# 14_BUZZER.net
KiCad netlist of a schematic drawn in Altium Designer
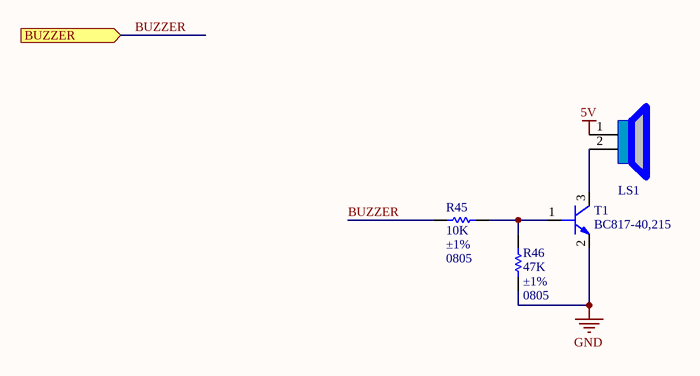
[diagram p0: 14.BUZZER.SchDoc]

(export (version "E")
  (design (tool "Eeschema 10.0.6"))
  (components
    (comp (ref "LS1")
      (value "BUZZER")
      (footprint "BUZZER_12MM")
      (description "AUDIO MAGNETIC INDICATOR 4-7V TH")
      (fields (field (name "PART NUMBER") "SAUD00001") (field (name "VOLTAGE") "5VDC"))
      (libsource (lib "ComponentDatabase") (part "BUZZER"))
    )
    (comp (ref "R45")
      (value "RES")
      (footprint "RESC2013X65N_EIA0805")
      (description "RES SMD 10K OHM 1% 1/8W 0805")
      (fields
        (field (name "PART NUMBER") "SRES03010098")
        (field (name "RESISTANCE (OHM)") "10K")
        (field (name "TOLERANCE") "±1%")
        (field (name "PACKAGE / CASE") "0805")
        (field (name "MANUFACTURER") "Yageo")
      )
      (libsource (lib "ComponentDatabase") (part "RES"))
    )
    (comp (ref "R46")
      (value "RES")
      (footprint "RESC2013X65N_EIA0805")
      (description "RES SMD 47K OHM 1% 1/8W 0805")
      (fields
        (field (name "PART NUMBER") "SRES03010114")
        (field (name "RESISTANCE (OHM)") "47K")
        (field (name "TOLERANCE") "±1%")
        (field (name "PACKAGE / CASE") "0805")
        (field (name "MANUFACTURER") "Yageo")
      )
      (libsource (lib "ComponentDatabase") (part "RES"))
    )
    (comp (ref "T1")
      (value "BC817-40")
      (footprint "SOT95P240X120-3N_SOT-23-3")
      (description "TRANS NPN 45V 0.5A SOT23")
      (fields
        (field (name "PART NUMBER") "SSEM00025")
        (field (name "MANUFACTURER") "NXP Semiconductors")
        (field (name "MANUFACTURER PART NUMBER") "BC817-40,215")
      )
      (libsource (lib "ComponentDatabase") (part "BC817-40"))
    )
  )
  (nets
    (net (code "1") (name "/BUZZER") (class "Default")
      (node (ref "R45") (pin "1") (pinfunction "1_1") (pintype "passive"))
    )
    (net (code "2") (name "5V") (class "Default")
      (node (ref "LS1") (pin "1") (pinfunction "+_1") (pintype "power_in"))
    )
    (net (code "3") (name "GND") (class "Default")
      (node (ref "R46") (pin "1") (pinfunction "1_1") (pintype "passive"))
      (node (ref "T1") (pin "2") (pinfunction "E_2") (pintype "passive"))
    )
    (net (code "4") (name "Net-(LS1--)") (class "Default")
      (node (ref "LS1") (pin "2") (pinfunction "-_2") (pintype "power_in"))
      (node (ref "T1") (pin "3") (pinfunction "C_3") (pintype "passive"))
    )
    (net (code "5") (name "Net-(T1-B)") (class "Default")
      (node (ref "R45") (pin "2") (pinfunction "2_2") (pintype "passive"))
      (node (ref "R46") (pin "2") (pinfunction "2_2") (pintype "passive"))
      (node (ref "T1") (pin "1") (pinfunction "B_1") (pintype "passive"))
    )
  )
)
